# TAStm32_v4.net
KiCad netlist of a schematic drawn in EAGLE
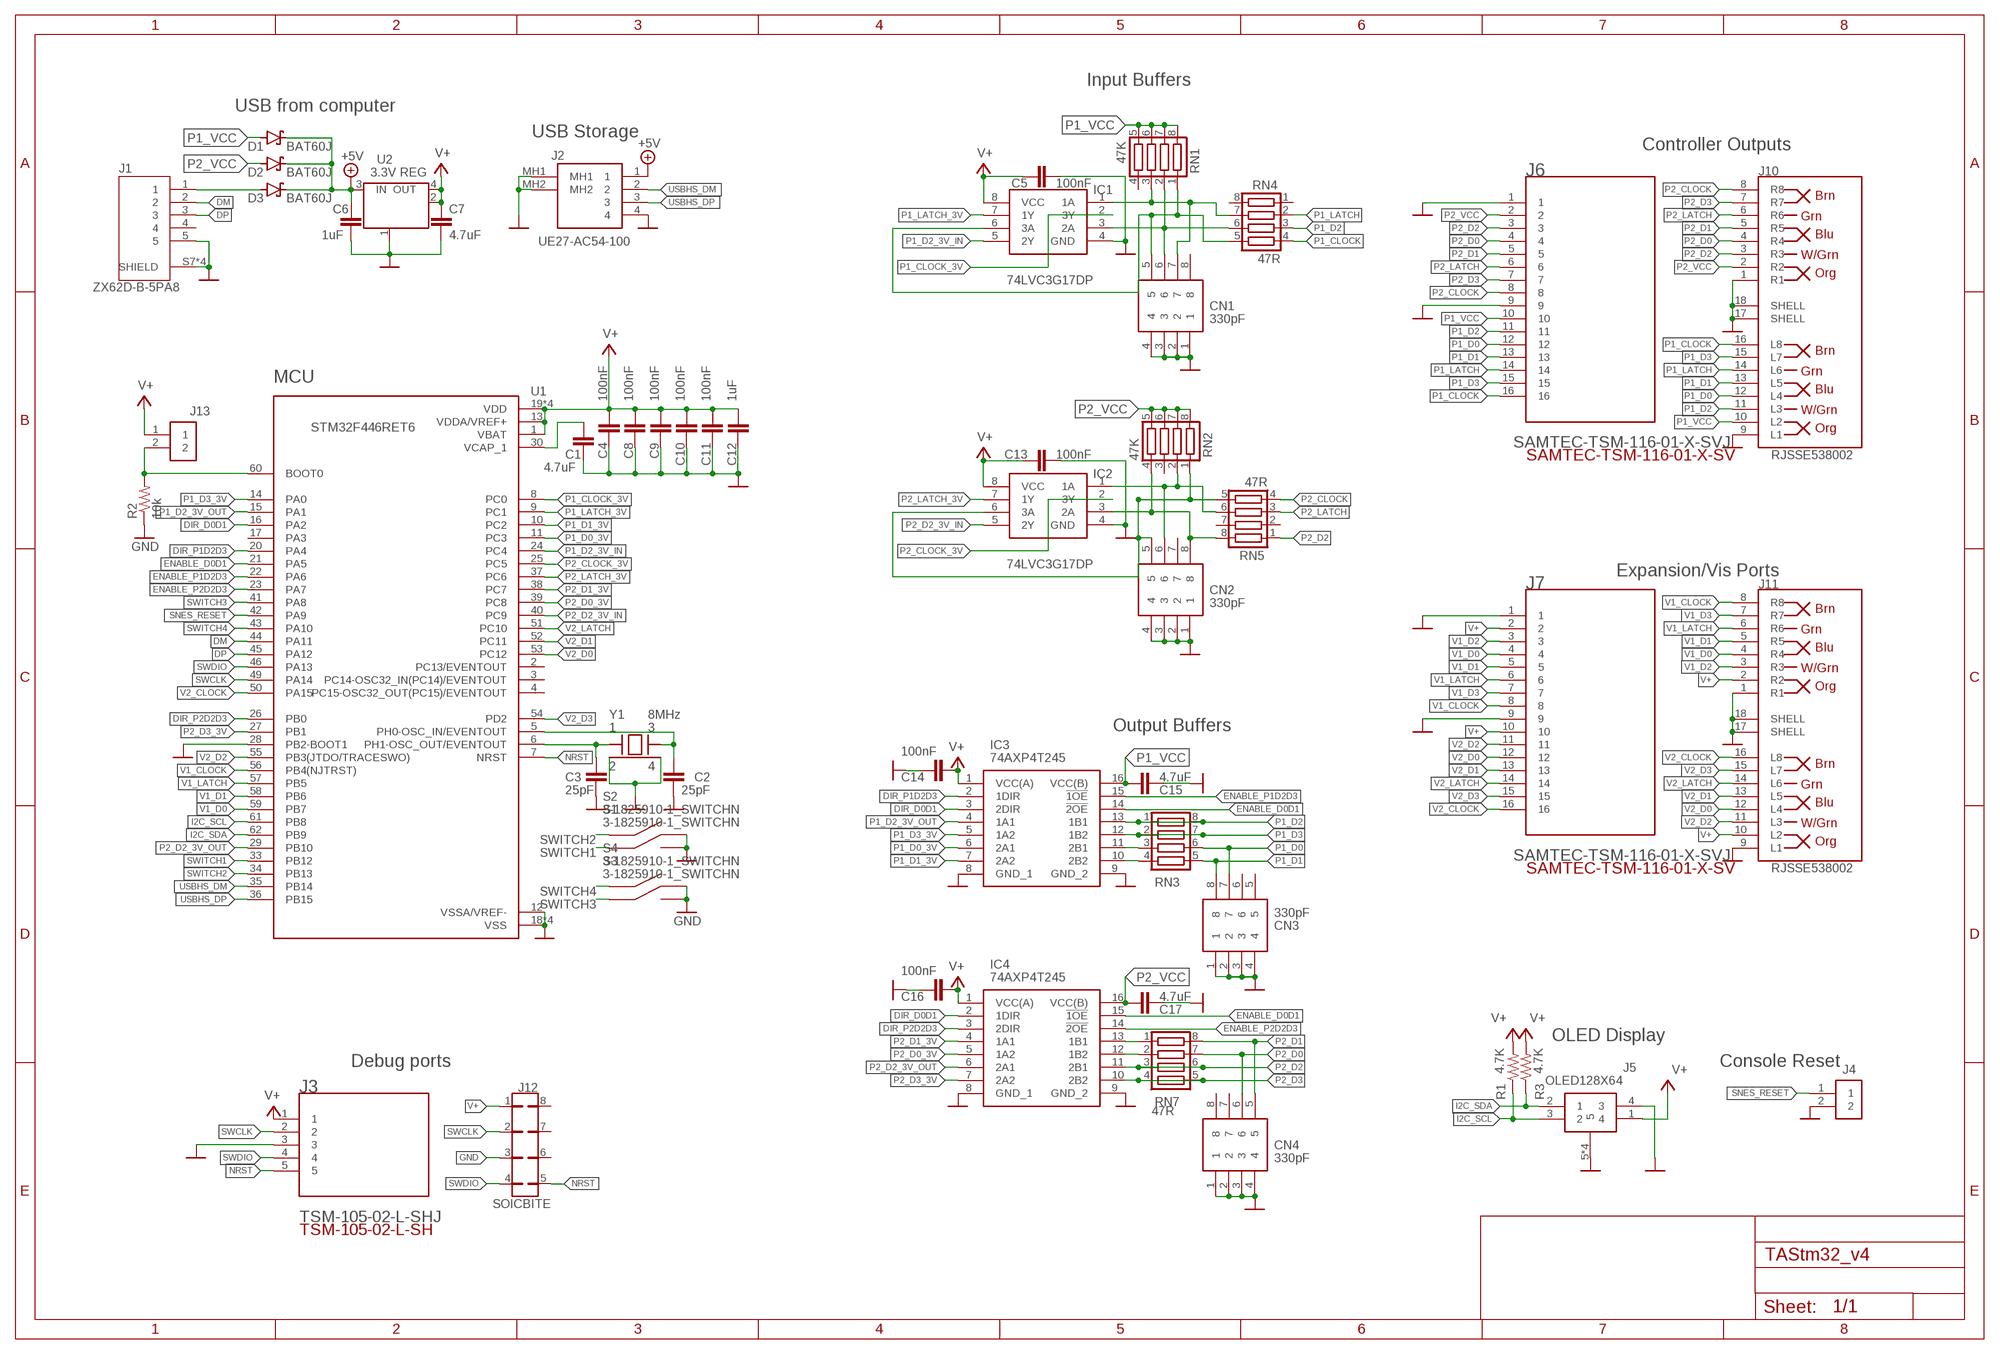
[diagram p0: schematic, sheet 1]

(export (version "E")
  (design (tool "Eeschema 10.0.6"))
  (components
    (comp (ref "C1")
      (value "4.7uF")
      (footprint "eagle-import:C0603K")
      (libsource (lib "eagle-import") (part "C-EUC0603K"))
    )
    (comp (ref "C2")
      (value "25pF")
      (footprint "eagle-import:C0603K")
      (libsource (lib "eagle-import") (part "C-EUC0603K"))
    )
    (comp (ref "C3")
      (value "25pF")
      (footprint "eagle-import:C0603K")
      (libsource (lib "eagle-import") (part "C-EUC0603K"))
    )
    (comp (ref "C4")
      (value "100nF")
      (footprint "eagle-import:C0603K")
      (libsource (lib "eagle-import") (part "C-EUC0603K"))
    )
    (comp (ref "C5")
      (value "100nF")
      (footprint "eagle-import:C0603K")
      (libsource (lib "eagle-import") (part "C-EUC0603K"))
    )
    (comp (ref "C6")
      (value "1uF")
      (footprint "eagle-import:C0603K")
      (libsource (lib "eagle-import") (part "C-EUC0603K"))
    )
    (comp (ref "C7")
      (value "4.7uF")
      (footprint "eagle-import:C0603K")
      (libsource (lib "eagle-import") (part "C-EUC0603K"))
    )
    (comp (ref "C8")
      (value "100nF")
      (footprint "eagle-import:C0603K")
      (libsource (lib "eagle-import") (part "C-EUC0603K"))
    )
    (comp (ref "C9")
      (value "100nF")
      (footprint "eagle-import:C0603K")
      (libsource (lib "eagle-import") (part "C-EUC0603K"))
    )
    (comp (ref "C10")
      (value "100nF")
      (footprint "eagle-import:C0603K")
      (libsource (lib "eagle-import") (part "C-EUC0603K"))
    )
    (comp (ref "C11")
      (value "100nF")
      (footprint "eagle-import:C0603K")
      (libsource (lib "eagle-import") (part "C-EUC0603K"))
    )
    (comp (ref "C12")
      (value "1uF")
      (footprint "eagle-import:C0603K")
      (libsource (lib "eagle-import") (part "C-EUC0603K"))
    )
    (comp (ref "C13")
      (value "100nF")
      (footprint "eagle-import:C0603K")
      (libsource (lib "eagle-import") (part "C-EUC0603K"))
    )
    (comp (ref "C14")
      (value "100nF")
      (footprint "eagle-import:C0603K")
      (libsource (lib "eagle-import") (part "C-EUC0603K"))
    )
    (comp (ref "C15")
      (value "4.7uF")
      (footprint "eagle-import:C0603K")
      (libsource (lib "eagle-import") (part "C-EUC0603K"))
    )
    (comp (ref "C16")
      (value "100nF")
      (footprint "eagle-import:C0603K")
      (libsource (lib "eagle-import") (part "C-EUC0603K"))
    )
    (comp (ref "C17")
      (value "4.7uF")
      (footprint "eagle-import:C0603K")
      (libsource (lib "eagle-import") (part "C-EUC0603K"))
    )
    (comp (ref "CN1")
      (value "330pF")
      (footprint "eagle-import:CA0612KRX7R7BB104")
      (fields
        (field (name "MANUFACTURER_PART_NUMBER") "CA0612KRX7R7BB104")
        (field (name "MOUSER_PART_NUMBER") "603-CA612KRX7R7BB104")
      )
      (libsource (lib "eagle-import") (part "CA0612KRX7R7BB104"))
    )
    (comp (ref "CN2")
      (value "330pF")
      (footprint "eagle-import:CA0612KRX7R7BB104")
      (fields
        (field (name "MANUFACTURER_PART_NUMBER") "CA0612KRX7R7BB104")
        (field (name "MOUSER_PART_NUMBER") "603-CA612KRX7R7BB104")
      )
      (libsource (lib "eagle-import") (part "CA0612KRX7R7BB104"))
    )
    (comp (ref "CN3")
      (value "330pF")
      (footprint "eagle-import:CA0612KRX7R7BB104")
      (fields
        (field (name "MANUFACTURER_PART_NUMBER") "CA0612KRX7R7BB104")
        (field (name "MOUSER_PART_NUMBER") "603-CA612KRX7R7BB104")
      )
      (libsource (lib "eagle-import") (part "CA0612KRX7R7BB104"))
    )
    (comp (ref "CN4")
      (value "330pF")
      (footprint "eagle-import:CA0612KRX7R7BB104")
      (fields
        (field (name "MANUFACTURER_PART_NUMBER") "CA0612KRX7R7BB104")
        (field (name "MOUSER_PART_NUMBER") "603-CA612KRX7R7BB104")
      )
      (libsource (lib "eagle-import") (part "CA0612KRX7R7BB104"))
    )
    (comp (ref "D1")
      (value "BAT60J")
      (footprint "eagle-import:DIODE_SOD323_ST")
      (libsource (lib "eagle-import") (part "DIODE_BAT60J"))
    )
    (comp (ref "D2")
      (value "BAT60J")
      (footprint "eagle-import:DIODE_SOD323_ST")
      (libsource (lib "eagle-import") (part "DIODE_BAT60J"))
    )
    (comp (ref "D3")
      (value "BAT60J")
      (footprint "eagle-import:DIODE_SOD323_ST")
      (libsource (lib "eagle-import") (part "DIODE_BAT60J"))
    )
    (comp (ref "IC1")
      (value "74LVC3G17DP")
      (footprint "eagle-import:SOP65P400X110-8N")
      (fields
        (field (name "MANUFACTURER_PART_NUMBER") "74HCT3G07DP-Q100H")
        (field (name "RS_PART_NUMBER") "1532947P")
      )
      (libsource (lib "eagle-import") (part "74HCT3G07DP-Q100H"))
    )
    (comp (ref "IC2")
      (value "74LVC3G17DP")
      (footprint "eagle-import:SOP65P400X110-8N")
      (fields
        (field (name "MANUFACTURER_PART_NUMBER") "74HCT3G07DP-Q100H")
        (field (name "RS_PART_NUMBER") "1532947P")
      )
      (libsource (lib "eagle-import") (part "74HCT3G07DP-Q100H"))
    )
    (comp (ref "IC3")
      (value "74AXP4T245")
      (footprint "eagle-import:SOP65P640X110-16N")
      (fields
        (field (name "MANUFACTURER_PART_NUMBER") "74AVCH4T245PW,118")
        (field (name "MOUSER_PART_NUMBER") "771-74AVCH4T245PW118")
      )
      (libsource (lib "eagle-import") (part "74AVCH4T245PW,118"))
    )
    (comp (ref "IC4")
      (value "74AXP4T245")
      (footprint "eagle-import:SOP65P640X110-16N")
      (fields
        (field (name "MANUFACTURER_PART_NUMBER") "74AVCH4T245PW,118")
        (field (name "MOUSER_PART_NUMBER") "771-74AVCH4T245PW118")
      )
      (libsource (lib "eagle-import") (part "74AVCH4T245PW,118"))
    )
    (comp (ref "J1")
      (value "ZX62D-B-5PA8")
      (footprint "eagle-import:HIROSE_ZX62D-B-5PA8")
      (fields (field (name "MF") "Hirose"))
      (libsource (lib "eagle-import") (part "ZX62D-B-5PA8"))
    )
    (comp (ref "J2")
      (value "UE27-AC54-100")
      (footprint "eagle-import:UE27AC54100")
      (fields (field (name "MOUSER_PART_NUMBER") "523-UE27-AC54-100"))
      (libsource (lib "eagle-import") (part "UE27-AC54-100"))
    )
    (comp (ref "J3")
      (value "TSM-105-02-L-SHJ")
      (footprint "eagle-import:TSM-105-02-L-SH")
      (fields (field (name "MF") "Samtec") (field (name "MP") "TSM-105-02-L-SH"))
      (libsource (lib "eagle-import") (part "TSM-105-02-L-SHJ"))
    )
    (comp (ref "J4")
      (value "CONSOLE_RESET")
      (footprint "eagle-import:SAMTEC-TSM-102-01-X-SH")
      (libsource (lib "eagle-import") (part "SAMTEC-TSM-102-01-X-SH_SAMTEC-TSM-102-01-X-SH"))
    )
    (comp (ref "J5")
      (value "OLED128X64")
      (footprint "eagle-import:OLED")
      (libsource (lib "eagle-import") (part "OLED128X64"))
    )
    (comp (ref "J6")
      (value "SAMTEC-TSM-116-01-X-SVJ")
      (footprint "eagle-import:SAMTEC-TSM-116-01-X-SV")
      (libsource (lib "eagle-import") (part "SAMTEC-TSM-116-01-X-SVJ"))
    )
    (comp (ref "J7")
      (value "SAMTEC-TSM-116-01-X-SVJ")
      (footprint "eagle-import:SAMTEC-TSM-116-01-X-SV")
      (libsource (lib "eagle-import") (part "SAMTEC-TSM-116-01-X-SVJ"))
    )
    (comp (ref "J10")
      (value "RJSSE538002")
      (footprint "eagle-import:AMPHENOL_RJSSE538002")
      (libsource (lib "eagle-import") (part "RJSSE538002_RJSSE538002"))
    )
    (comp (ref "J11")
      (value "RJSSE538002")
      (footprint "eagle-import:AMPHENOL_RJSSE538002")
      (libsource (lib "eagle-import") (part "RJSSE538002_RJSSE538002"))
    )
    (comp (ref "J12")
      (value "SOICBITE")
      (footprint "eagle-import:SOICBITE")
      (libsource (lib "eagle-import") (part "SOICBITE"))
    )
    (comp (ref "J13")
      (value "CONSOLE_RESET")
      (footprint "eagle-import:SAMTEC-TSM-102-01-X-SH")
      (libsource (lib "eagle-import") (part "SAMTEC-TSM-102-01-X-SH_SAMTEC-TSM-102-01-X-SH"))
    )
    (comp (ref "R1")
      (value "4.7K")
      (footprint "eagle-import:R0805")
      (libsource (lib "eagle-import") (part "R-US_R0805"))
    )
    (comp (ref "R2")
      (value "10k")
      (footprint "eagle-import:R0805")
      (libsource (lib "eagle-import") (part "R-US_R0805"))
    )
    (comp (ref "R3")
      (value "4.7K")
      (footprint "eagle-import:R0805")
      (libsource (lib "eagle-import") (part "R-US_R0805"))
    )
    (comp (ref "RN1")
      (value "47K")
      (footprint "eagle-import:CTS742C083")
      (libsource (lib "eagle-import") (part "CTS742C083"))
    )
    (comp (ref "RN2")
      (value "47K")
      (footprint "eagle-import:CTS742C083")
      (libsource (lib "eagle-import") (part "CTS742C083"))
    )
    (comp (ref "RN3")
      (value "CTS742C083")
      (footprint "eagle-import:CTS742C083")
      (libsource (lib "eagle-import") (part "CTS742C083"))
    )
    (comp (ref "RN4")
      (value "47R")
      (footprint "eagle-import:CTS742C083")
      (libsource (lib "eagle-import") (part "CTS742C083"))
    )
    (comp (ref "RN5")
      (value "47R")
      (footprint "eagle-import:CTS742C083")
      (libsource (lib "eagle-import") (part "CTS742C083"))
    )
    (comp (ref "RN7")
      (value "47R")
      (footprint "eagle-import:CTS742C083")
      (libsource (lib "eagle-import") (part "CTS742C083"))
    )
    (comp (ref "S1")
      (value "3-1825910-1_SWITCHN")
      (footprint "eagle-import:3-1825910-1_318259101")
      (libsource (lib "eagle-import") (part "3-1825910-1_SWITCHN"))
    )
    (comp (ref "S2")
      (value "3-1825910-1_SWITCHN")
      (footprint "eagle-import:3-1825910-1_318259101")
      (libsource (lib "eagle-import") (part "3-1825910-1_SWITCHN"))
    )
    (comp (ref "S3")
      (value "3-1825910-1_SWITCHN")
      (footprint "eagle-import:3-1825910-1_318259101")
      (libsource (lib "eagle-import") (part "3-1825910-1_SWITCHN"))
    )
    (comp (ref "S4")
      (value "3-1825910-1_SWITCHN")
      (footprint "eagle-import:3-1825910-1_318259101")
      (libsource (lib "eagle-import") (part "3-1825910-1_SWITCHN"))
    )
    (comp (ref "U1")
      (value "STM32F446RET6")
      (footprint "eagle-import:QFP50P1200X1200X160-64N")
      (libsource (lib "eagle-import") (part "STM32F446RET7"))
    )
    (comp (ref "U2")
      (value "3.3V REG")
      (footprint "eagle-import:SOT223")
      (libsource (lib "eagle-import") (part "MC33269ST-3.3T3"))
    )
    (comp (ref "Y1")
      (value "8MHz")
      (footprint "eagle-import:DFN-4")
      (libsource (lib "eagle-import") (part "ABMM-8.000MHZ-B2-T_ABMM-8.000MHZ-B2-T"))
    )
  )
  (nets
    (net (code "1") (name "+5V") (class "Default")
      (node (ref "C6") (pin "2") (pinfunction "2_2") (pintype "passive"))
      (node (ref "D1") (pin "C") (pinfunction "C_C") (pintype "passive"))
      (node (ref "D2") (pin "C") (pinfunction "C_C") (pintype "passive"))
      (node (ref "D3") (pin "C") (pinfunction "C_C") (pintype "passive"))
      (node (ref "J2") (pin "1") (pinfunction "1_1") (pintype "bidirectional"))
      (node (ref "U2") (pin "3") (pinfunction "IN_3") (pintype "input"))
    )
    (net (code "2") (name "DIR_D0D1") (class "Default")
      (node (ref "IC3") (pin "3") (pinfunction "2DIR_3") (pintype "bidirectional"))
      (node (ref "IC4") (pin "2") (pinfunction "1DIR_2") (pintype "bidirectional"))
      (node (ref "U1") (pin "16") (pinfunction "PA2_16") (pintype "bidirectional"))
    )
    (net (code "3") (name "DIR_P1D2D3") (class "Default")
      (node (ref "IC3") (pin "2") (pinfunction "1DIR_2") (pintype "bidirectional"))
      (node (ref "U1") (pin "20") (pinfunction "PA4_20") (pintype "bidirectional"))
    )
    (net (code "4") (name "DIR_P2D2D3") (class "Default")
      (node (ref "IC4") (pin "3") (pinfunction "2DIR_3") (pintype "bidirectional"))
      (node (ref "U1") (pin "26") (pinfunction "PB0_26") (pintype "bidirectional"))
    )
    (net (code "5") (name "DM") (class "Default")
      (node (ref "J1") (pin "2") (pinfunction "2_2") (pintype "passive"))
      (node (ref "U1") (pin "44") (pinfunction "PA11_44") (pintype "bidirectional"))
    )
    (net (code "6") (name "DP") (class "Default")
      (node (ref "J1") (pin "3") (pinfunction "3_3") (pintype "passive"))
      (node (ref "U1") (pin "45") (pinfunction "PA12_45") (pintype "bidirectional"))
    )
    (net (code "7") (name "ENABLE_D0D1") (class "Default")
      (node (ref "IC3") (pin "14") (pinfunction "~{2OE}_14") (pintype "bidirectional"))
      (node (ref "IC4") (pin "15") (pinfunction "~{1OE}_15") (pintype "bidirectional"))
      (node (ref "U1") (pin "21") (pinfunction "PA5_21") (pintype "bidirectional"))
    )
    (net (code "8") (name "ENABLE_P1D2D3") (class "Default")
      (node (ref "IC3") (pin "15") (pinfunction "~{1OE}_15") (pintype "bidirectional"))
      (node (ref "U1") (pin "22") (pinfunction "PA6_22") (pintype "bidirectional"))
    )
    (net (code "9") (name "ENABLE_P2D2D3") (class "Default")
      (node (ref "IC4") (pin "14") (pinfunction "~{2OE}_14") (pintype "bidirectional"))
      (node (ref "U1") (pin "23") (pinfunction "PA7_23") (pintype "bidirectional"))
    )
    (net (code "10") (name "GND") (class "Default")
      (node (ref "C1") (pin "2") (pinfunction "2_2") (pintype "passive"))
      (node (ref "C10") (pin "1") (pinfunction "1_1") (pintype "passive"))
      (node (ref "C11") (pin "1") (pinfunction "1_1") (pintype "passive"))
      (node (ref "C12") (pin "1") (pinfunction "1_1") (pintype "passive"))
      (node (ref "C13") (pin "2") (pinfunction "2_2") (pintype "passive"))
      (node (ref "C14") (pin "1") (pinfunction "1_1") (pintype "passive"))
      (node (ref "C15") (pin "2") (pinfunction "2_2") (pintype "passive"))
      (node (ref "C16") (pin "1") (pinfunction "1_1") (pintype "passive"))
      (node (ref "C17") (pin "2") (pinfunction "2_2") (pintype "passive"))
      (node (ref "C2") (pin "1") (pinfunction "1_1") (pintype "passive"))
      (node (ref "C3") (pin "1") (pinfunction "1_1") (pintype "passive"))
      (node (ref "C4") (pin "1") (pinfunction "1_1") (pintype "passive"))
      (node (ref "C5") (pin "2") (pinfunction "2_2") (pintype "passive"))
      (node (ref "C6") (pin "1") (pinfunction "1_1") (pintype "passive"))
      (node (ref "C7") (pin "1") (pinfunction "1_1") (pintype "passive"))
      (node (ref "C8") (pin "1") (pinfunction "1_1") (pintype "passive"))
      (node (ref "C9") (pin "1") (pinfunction "1_1") (pintype "passive"))
      (node (ref "CN1") (pin "1") (pinfunction "1_1") (pintype "bidirectional"))
      (node (ref "CN1") (pin "2") (pinfunction "2_2") (pintype "bidirectional"))
      (node (ref "CN1") (pin "3") (pinfunction "3_3") (pintype "bidirectional"))
      (node (ref "CN1") (pin "4") (pinfunction "4_4") (pintype "bidirectional"))
      (node (ref "CN2") (pin "1") (pinfunction "1_1") (pintype "bidirectional"))
      (node (ref "CN2") (pin "2") (pinfunction "2_2") (pintype "bidirectional"))
      (node (ref "CN2") (pin "3") (pinfunction "3_3") (pintype "bidirectional"))
      (node (ref "CN2") (pin "4") (pinfunction "4_4") (pintype "bidirectional"))
      (node (ref "CN3") (pin "1") (pinfunction "1_1") (pintype "bidirectional"))
      (node (ref "CN3") (pin "2") (pinfunction "2_2") (pintype "bidirectional"))
      (node (ref "CN3") (pin "3") (pinfunction "3_3") (pintype "bidirectional"))
      (node (ref "CN3") (pin "4") (pinfunction "4_4") (pintype "bidirectional"))
      (node (ref "CN4") (pin "1") (pinfunction "1_1") (pintype "bidirectional"))
      (node (ref "CN4") (pin "2") (pinfunction "2_2") (pintype "bidirectional"))
      (node (ref "CN4") (pin "3") (pinfunction "3_3") (pintype "bidirectional"))
      (node (ref "CN4") (pin "4") (pinfunction "4_4") (pintype "bidirectional"))
      (node (ref "IC1") (pin "4") (pinfunction "GND_4") (pintype "bidirectional"))
      (node (ref "IC2") (pin "4") (pinfunction "GND_4") (pintype "bidirectional"))
      (node (ref "IC3") (pin "8") (pinfunction "GND_1_8") (pintype "bidirectional"))
      (node (ref "IC3") (pin "9") (pinfunction "GND_2_9") (pintype "bidirectional"))
      (node (ref "IC4") (pin "8") (pinfunction "GND_1_8") (pintype "bidirectional"))
      (node (ref "IC4") (pin "9") (pinfunction "GND_2_9") (pintype "bidirectional"))
      (node (ref "J1") (pin "5") (pinfunction "5_5") (pintype "passive"))
      (node (ref "J1") (pin "S10") (pinfunction "SHIELD_S10") (pintype "power_in"))
      (node (ref "J1") (pin "S7") (pinfunction "SHIELD_S7") (pintype "power_in"))
      (node (ref "J1") (pin "S8") (pinfunction "SHIELD_S8") (pintype "power_in"))
      (node (ref "J1") (pin "S9") (pinfunction "SHIELD_S9") (pintype "power_in"))
      (node (ref "J10") (pin "1") (pinfunction "R1_1") (pintype "bidirectional"))
      (node (ref "J10") (pin "17") (pinfunction "SHELL_17") (pintype "passive"))
      (node (ref "J10") (pin "18") (pinfunction "SHELL_18") (pintype "passive"))
      (node (ref "J10") (pin "9") (pinfunction "L1_9") (pintype "bidirectional"))
      (node (ref "J11") (pin "1") (pinfunction "R1_1") (pintype "bidirectional"))
      (node (ref "J11") (pin "17") (pinfunction "SHELL_17") (pintype "passive"))
      (node (ref "J11") (pin "18") (pinfunction "SHELL_18") (pintype "passive"))
      (node (ref "J11") (pin "9") (pinfunction "L1_9") (pintype "bidirectional"))
      (node (ref "J12") (pin "3") (pinfunction "P$3_3") (pintype "passive"))
      (node (ref "J2") (pin "4") (pinfunction "4_4") (pintype "bidirectional"))
      (node (ref "J2") (pin "MH1") (pinfunction "MH1_MH1") (pintype "bidirectional"))
      (node (ref "J2") (pin "MH2") (pinfunction "MH2_MH2") (pintype "bidirectional"))
      (node (ref "J3") (pin "3") (pinfunction "3_3") (pintype "bidirectional"))
      (node (ref "J4") (pin "2") (pinfunction "2_2") (pintype "bidirectional"))
      (node (ref "J5") (pin "4") (pinfunction "3_4") (pintype "bidirectional"))
      (node (ref "J5") (pin "5") (pinfunction "5_5") (pintype "bidirectional"))
      (node (ref "J5") (pin "6") (pinfunction "5_6") (pintype "bidirectional"))
      (node (ref "J5") (pin "7") (pinfunction "5_7") (pintype "bidirectional"))
      (node (ref "J5") (pin "8") (pinfunction "5_8") (pintype "bidirectional"))
      (node (ref "J6") (pin "1") (pinfunction "1_1") (pintype "bidirectional"))
      (node (ref "J6") (pin "9") (pinfunction "9_9") (pintype "bidirectional"))
      (node (ref "J7") (pin "1") (pinfunction "1_1") (pintype "bidirectional"))
      (node (ref "J7") (pin "9") (pinfunction "9_9") (pintype "bidirectional"))
      (node (ref "R2") (pin "1") (pinfunction "1_1") (pintype "passive"))
      (node (ref "S1") (pin "3") (pinfunction "P$2_3") (pintype "bidirectional"))
      (node (ref "S1") (pin "4") (pinfunction "P$2_4") (pintype "bidirectional"))
      (node (ref "S2") (pin "3") (pinfunction "P$2_3") (pintype "bidirectional"))
      (node (ref "S2") (pin "4") (pinfunction "P$2_4") (pintype "bidirectional"))
      (node (ref "S3") (pin "3") (pinfunction "P$2_3") (pintype "bidirectional"))
      (node (ref "S3") (pin "4") (pinfunction "P$2_4") (pintype "bidirectional"))
      (node (ref "S4") (pin "3") (pinfunction "P$2_3") (pintype "bidirectional"))
      (node (ref "S4") (pin "4") (pinfunction "P$2_4") (pintype "bidirectional"))
      (node (ref "U1") (pin "12") (pinfunction "VSSA/VREF-_12") (pintype "power_in"))
      (node (ref "U1") (pin "18") (pinfunction "VSS_18") (pintype "power_in"))
      (node (ref "U1") (pin "28") (pinfunction "PB2-BOOT1_28") (pintype "bidirectional"))
      (node (ref "U1") (pin "31") (pinfunction "VSS_31") (pintype "power_in"))
      (node (ref "U1") (pin "47") (pinfunction "VSS_47") (pintype "power_in"))
      (node (ref "U1") (pin "63") (pinfunction "VSS_63") (pintype "power_in"))
      (node (ref "U2") (pin "1") (pinfunction "GND/ADJ_1") (pintype "input"))
      (node (ref "Y1") (pin "2") (pinfunction "2_2") (pintype "bidirectional"))
      (node (ref "Y1") (pin "4") (pinfunction "4_4") (pintype "bidirectional"))
    )
    (net (code "11") (name "I2C_SCL") (class "Default")
      (node (ref "J5") (pin "3") (pinfunction "2_3") (pintype "bidirectional"))
      (node (ref "R1") (pin "1") (pinfunction "1_1") (pintype "passive"))
      (node (ref "U1") (pin "61") (pinfunction "PB8_61") (pintype "bidirectional"))
    )
    (net (code "12") (name "I2C_SDA") (class "Default")
      (node (ref "J5") (pin "2") (pinfunction "1_2") (pintype "bidirectional"))
      (node (ref "R3") (pin "1") (pinfunction "1_1") (pintype "passive"))
      (node (ref "U1") (pin "62") (pinfunction "PB9_62") (pintype "bidirectional"))
    )
    (net (code "13") (name "NRST") (class "Default")
      (node (ref "J12") (pin "5") (pinfunction "P$5_5") (pintype "passive"))
      (node (ref "J3") (pin "5") (pinfunction "5_5") (pintype "bidirectional"))
      (node (ref "U1") (pin "7") (pinfunction "NRST_7") (pintype "bidirectional"))
    )
    (net (code "14") (name "Net-(D3-PadA)") (class "Default")
      (node (ref "D3") (pin "A") (pinfunction "A_A") (pintype "passive"))
      (node (ref "J1") (pin "1") (pinfunction "1_1") (pintype "passive"))
    )
    (net (code "15") (name "Net-(IC1-1A)") (class "Default")
      (node (ref "CN1") (pin "7") (pinfunction "7_7") (pintype "bidirectional"))
      (node (ref "IC1") (pin "1") (pinfunction "1A_1") (pintype "bidirectional"))
      (node (ref "RN1") (pin "3") (pinfunction "3_3") (pintype "passive"))
      (node (ref "RN4") (pin "7") (pinfunction "7_7") (pintype "passive"))
    )
    (net (code "16") (name "Net-(IC1-2A)") (class "Default")
      (node (ref "CN1") (pin "6") (pinfunction "6_6") (pintype "bidirectional"))
      (node (ref "IC1") (pin "3") (pinfunction "2A_3") (pintype "bidirectional"))
      (node (ref "RN1") (pin "2") (pinfunction "2_2") (pintype "passive"))
      (node (ref "RN4") (pin "6") (pinfunction "6_6") (pintype "passive"))
    )
    (net (code "17") (name "Net-(IC1-3A)") (class "Default")
      (node (ref "CN1") (pin "5") (pinfunction "5_5") (pintype "bidirectional"))
      (node (ref "IC1") (pin "6") (pinfunction "3A_6") (pintype "bidirectional"))
      (node (ref "RN1") (pin "1") (pinfunction "1_1") (pintype "passive"))
      (node (ref "RN4") (pin "5") (pinfunction "5_5") (pintype "passive"))
    )
    (net (code "18") (name "Net-(IC2-1A)") (class "Default")
      (node (ref "CN2") (pin "6") (pinfunction "6_6") (pintype "bidirectional"))
      (node (ref "IC2") (pin "1") (pinfunction "1A_1") (pintype "bidirectional"))
      (node (ref "RN2") (pin "2") (pinfunction "2_2") (pintype "passive"))
      (node (ref "RN5") (pin "6") (pinfunction "6_6") (pintype "passive"))
    )
    (net (code "19") (name "Net-(IC2-2A)") (class "Default")
      (node (ref "CN2") (pin "8") (pinfunction "8_8") (pintype "bidirectional"))
      (node (ref "IC2") (pin "3") (pinfunction "2A_3") (pintype "bidirectional"))
      (node (ref "RN2") (pin "4") (pinfunction "4_4") (pintype "passive"))
      (node (ref "RN5") (pin "8") (pinfunction "8_8") (pintype "passive"))
    )
    (net (code "20") (name "Net-(IC2-3A)") (class "Default")
      (node (ref "CN2") (pin "5") (pinfunction "5_5") (pintype "bidirectional"))
      (node (ref "IC2") (pin "6") (pinfunction "3A_6") (pintype "bidirectional"))
      (node (ref "RN2") (pin "1") (pinfunction "1_1") (pintype "passive"))
      (node (ref "RN5") (pin "5") (pinfunction "5_5") (pintype "passive"))
    )
    (net (code "21") (name "Net-(IC3-2B1)") (class "Default")
      (node (ref "IC3") (pin "11") (pinfunction "2B1_11") (pintype "bidirectional"))
      (node (ref "RN3") (pin "3") (pinfunction "3_3") (pintype "passive"))
    )
    (net (code "22") (name "Net-(IC3-2B2)") (class "Default")
      (node (ref "IC3") (pin "10") (pinfunction "2B2_10") (pintype "bidirectional"))
      (node (ref "RN3") (pin "4") (pinfunction "4_4") (pintype "passive"))
    )
    (net (code "23") (name "Net-(IC4-1B1)") (class "Default")
      (node (ref "IC4") (pin "13") (pinfunction "1B1_13") (pintype "bidirectional"))
      (node (ref "RN7") (pin "1") (pinfunction "1_1") (pintype "passive"))
    )
    (net (code "24") (name "Net-(IC4-1B2)") (class "Default")
      (node (ref "IC4") (pin "12") (pinfunction "1B2_12") (pintype "bidirectional"))
      (node (ref "RN7") (pin "2") (pinfunction "2_2") (pintype "passive"))
    )
    (net (code "25") (name "Net-(U1-BOOT0)") (class "Default")
      (node (ref "J13") (pin "2") (pinfunction "2_2") (pintype "bidirectional"))
      (node (ref "R2") (pin "2") (pinfunction "2_2") (pintype "passive"))
      (node (ref "U1") (pin "60") (pinfunction "BOOT0_60") (pintype "input"))
    )
    (net (code "26") (name "Net-(U1-PH0-OSC_IN{slash}EVENTOUT)") (class "Default")
      (node (ref "C2") (pin "2") (pinfunction "2_2") (pintype "passive"))
      (node (ref "U1") (pin "5") (pinfunction "PH0-OSC_IN/EVENTOUT_5") (pintype "bidirectional"))
      (node (ref "Y1") (pin "3") (pinfunction "3_3") (pintype "bidirectional"))
    )
    (net (code "27") (name "Net-(U1-PH1-OSC_OUT{slash}EVENTOUT)") (class "Default")
      (node (ref "C3") (pin "2") (pinfunction "2_2") (pintype "passive"))
      (node (ref "U1") (pin "6") (pinfunction "PH1-OSC_OUT/EVENTOUT_6") (pintype "bidirectional"))
      (node (ref "Y1") (pin "1") (pinfunction "1_1") (pintype "bidirectional"))
    )
    (net (code "28") (name "Net-(U1-VCAP_1)") (class "Default")
      (node (ref "C1") (pin "1") (pinfunction "1_1") (pintype "passive"))
      (node (ref "U1") (pin "30") (pinfunction "VCAP_1_30") (pintype "power_in"))
    )
    (net (code "29") (name "P1_CLOCK") (class "Default")
      (node (ref "J10") (pin "16") (pinfunction "L8_16") (pintype "bidirectional"))
      (node (ref "J6") (pin "16") (pinfunction "16_16") (pintype "bidirectional"))
      (node (ref "RN4") (pin "4") (pinfunction "4_4") (pintype "passive"))
    )
    (net (code "30") (name "P1_CLOCK_3V") (class "Default")
      (node (ref "IC1") (pin "2") (pinfunction "3Y_2") (pintype "bidirectional"))
      (node (ref "U1") (pin "8") (pinfunction "PC0_8") (pintype "bidirectional"))
    )
    (net (code "31") (name "P1_D0") (class "Default")
      (node (ref "CN3") (pin "7") (pinfunction "7_7") (pintype "bidirectional"))
      (node (ref "J10") (pin "12") (pinfunction "L4_12") (pintype "bidirectional"))
      (node (ref "J6") (pin "12") (pinfunction "12_12") (pintype "bidirectional"))
      (node (ref "RN3") (pin "6") (pinfunction "6_6") (pintype "passive"))
    )
    (net (code "32") (name "P1_D0_3V") (class "Default")
      (node (ref "IC3") (pin "6") (pinfunction "2A1_6") (pintype "bidirectional"))
      (node (ref "U1") (pin "11") (pinfunction "PC3_11") (pintype "bidirectional"))
    )
    (net (code "33") (name "P1_D1") (class "Default")
      (node (ref "CN3") (pin "8") (pinfunction "8_8") (pintype "bidirectional"))
      (node (ref "J10") (pin "13") (pinfunction "L5_13") (pintype "bidirectional"))
      (node (ref "J6") (pin "13") (pinfunction "13_13") (pintype "bidirectional"))
      (node (ref "RN3") (pin "5") (pinfunction "5_5") (pintype "passive"))
    )
    (net (code "34") (name "P1_D1_3V") (class "Default")
      (node (ref "IC3") (pin "7") (pinfunction "2A2_7") (pintype "bidirectional"))
      (node (ref "U1") (pin "10") (pinfunction "PC2_10") (pintype "bidirectional"))
    )
    (net (code "35") (name "P1_D2") (class "Default")
      (node (ref "IC3") (pin "13") (pinfunction "1B1_13") (pintype "bidirectional"))
      (node (ref "J10") (pin "11") (pinfunction "L3_11") (pintype "bidirectional"))
      (node (ref "J6") (pin "11") (pinfunction "11_11") (pintype "bidirectional"))
      (node (ref "RN3") (pin "1") (pinfunction "1_1") (pintype "passive"))
      (node (ref "RN3") (pin "8") (pinfunction "8_8") (pintype "passive"))
      (node (ref "RN4") (pin "3") (pinfunction "3_3") (pintype "passive"))
    )
    (net (code "36") (name "P1_D2_3V_IN") (class "Default")
      (node (ref "IC1") (pin "5") (pinfunction "2Y_5") (pintype "bidirectional"))
      (node (ref "U1") (pin "24") (pinfunction "PC4_24") (pintype "bidirectional"))
    )
    (net (code "37") (name "P1_D2_3V_OUT") (class "Default")
      (node (ref "IC3") (pin "4") (pinfunction "1A1_4") (pintype "bidirectional"))
      (node (ref "U1") (pin "15") (pinfunction "PA1_15") (pintype "bidirectional"))
    )
    (net (code "38") (name "P1_D3") (class "Default")
      (node (ref "IC3") (pin "12") (pinfunction "1B2_12") (pintype "bidirectional"))
      (node (ref "J10") (pin "15") (pinfunction "L7_15") (pintype "bidirectional"))
      (node (ref "J6") (pin "15") (pinfunction "15_15") (pintype "bidirectional"))
      (node (ref "RN3") (pin "2") (pinfunction "2_2") (pintype "passive"))
      (node (ref "RN3") (pin "7") (pinfunction "7_7") (pintype "passive"))
    )
    (net (code "39") (name "P1_D3_3V") (class "Default")
      (node (ref "IC3") (pin "5") (pinfunction "1A2_5") (pintype "bidirectional"))
      (node (ref "U1") (pin "14") (pinfunction "PA0_14") (pintype "bidirectional"))
    )
    (net (code "40") (name "P1_LATCH") (class "Default")
      (node (ref "J10") (pin "14") (pinfunction "L6_14") (pintype "bidirectional"))
      (node (ref "J6") (pin "14") (pinfunction "14_14") (pintype "bidirectional"))
      (node (ref "RN4") (pin "2") (pinfunction "2_2") (pintype "passive"))
    )
    (net (code "41") (name "P1_LATCH_3V") (class "Default")
      (node (ref "IC1") (pin "7") (pinfunction "1Y_7") (pintype "bidirectional"))
      (node (ref "U1") (pin "9") (pinfunction "PC1_9") (pintype "bidirectional"))
    )
    (net (code "42") (name "P1_VCC") (class "Default")
      (node (ref "C15") (pin "1") (pinfunction "1_1") (pintype "passive"))
      (node (ref "D1") (pin "A") (pinfunction "A_A") (pintype "passive"))
      (node (ref "IC3") (pin "16") (pinfunction "VCC(B)_16") (pintype "bidirectional"))
      (node (ref "J10") (pin "10") (pinfunction "L2_10") (pintype "bidirectional"))
      (node (ref "J6") (pin "10") (pinfunction "10_10") (pintype "bidirectional"))
      (node (ref "RN1") (pin "5") (pinfunction "5_5") (pintype "passive"))
      (node (ref "RN1") (pin "6") (pinfunction "6_6") (pintype "passive"))
      (node (ref "RN1") (pin "7") (pinfunction "7_7") (pintype "passive"))
      (node (ref "RN1") (pin "8") (pinfunction "8_8") (pintype "passive"))
    )
    (net (code "43") (name "P2_CLOCK") (class "Default")
      (node (ref "J10") (pin "8") (pinfunction "R8_8") (pintype "bidirectional"))
      (node (ref "J6") (pin "8") (pinfunction "8_8") (pintype "bidirectional"))
      (node (ref "RN5") (pin "4") (pinfunction "4_4") (pintype "passive"))
    )
    (net (code "44") (name "P2_CLOCK_3V") (class "Default")
      (node (ref "IC2") (pin "2") (pinfunction "3Y_2") (pintype "bidirectional"))
      (node (ref "U1") (pin "25") (pinfunction "PC5_25") (pintype "bidirectional"))
    )
    (net (code "45") (name "P2_D0") (class "Default")
      (node (ref "CN4") (pin "6") (pinfunction "6_6") (pintype "bidirectional"))
      (node (ref "J10") (pin "4") (pinfunction "R4_4") (pintype "bidirectional"))
      (node (ref "J6") (pin "4") (pinfunction "4_4") (pintype "bidirectional"))
      (node (ref "RN7") (pin "7") (pinfunction "7_7") (pintype "passive"))
    )
    (net (code "46") (name "P2_D0_3V") (class "Default")
      (node (ref "IC4") (pin "5") (pinfunction "1A2_5") (pintype "bidirectional"))
      (node (ref "U1") (pin "39") (pinfunction "PC8_39") (pintype "bidirectional"))
    )
    (net (code "47") (name "P2_D1") (class "Default")
      (node (ref "CN4") (pin "5") (pinfunction "5_5") (pintype "bidirectional"))
      (node (ref "J10") (pin "5") (pinfunction "R5_5") (pintype "bidirectional"))
      (node (ref "J6") (pin "5") (pinfunction "5_5") (pintype "bidirectional"))
      (node (ref "RN7") (pin "8") (pinfunction "8_8") (pintype "passive"))
    )
    (net (code "48") (name "P2_D1_3V") (class "Default")
      (node (ref "IC4") (pin "4") (pinfunction "1A1_4") (pintype "bidirectional"))
      (node (ref "U1") (pin "38") (pinfunction "PC7_38") (pintype "bidirectional"))
    )
    (net (code "49") (name "P2_D2") (class "Default")
      (node (ref "IC4") (pin "11") (pinfunction "2B1_11") (pintype "bidirectional"))
      (node (ref "J10") (pin "3") (pinfunction "R3_3") (pintype "bidirectional"))
      (node (ref "J6") (pin "3") (pinfunction "3_3") (pintype "bidirectional"))
      (node (ref "RN5") (pin "1") (pinfunction "1_1") (pintype "passive"))
      (node (ref "RN7") (pin "3") (pinfunction "3_3") (pintype "passive"))
      (node (ref "RN7") (pin "6") (pinfunction "6_6") (pintype "passive"))
    )
    (net (code "50") (name "P2_D2_3V_IN") (class "Default")
      (node (ref "IC2") (pin "5") (pinfunction "2Y_5") (pintype "bidirectional"))
      (node (ref "U1") (pin "40") (pinfunction "PC9_40") (pintype "bidirectional"))
    )
    (net (code "51") (name "P2_D2_3V_OUT") (class "Default")
      (node (ref "IC4") (pin "6") (pinfunction "2A1_6") (pintype "bidirectional"))
      (node (ref "U1") (pin "29") (pinfunction "PB10_29") (pintype "bidirectional"))
    )
    (net (code "52") (name "P2_D3") (class "Default")
      (node (ref "IC4") (pin "10") (pinfunction "2B2_10") (pintype "bidirectional"))
      (node (ref "J10") (pin "7") (pinfunction "R7_7") (pintype "bidirectional"))
      (node (ref "J6") (pin "7") (pinfunction "7_7") (pintype "bidirectional"))
      (node (ref "RN7") (pin "4") (pinfunction "4_4") (pintype "passive"))
      (node (ref "RN7") (pin "5") (pinfunction "5_5") (pintype "passive"))
    )
    (net (code "53") (name "P2_D3_3V") (class "Default")
      (node (ref "IC4") (pin "7") (pinfunction "2A2_7") (pintype "bidirectional"))
      (node (ref "U1") (pin "27") (pinfunction "PB1_27") (pintype "bidirectional"))
    )
    (net (code "54") (name "P2_LATCH") (class "Default")
      (node (ref "J10") (pin "6") (pinfunction "R6_6") (pintype "bidirectional"))
      (node (ref "J6") (pin "6") (pinfunction "6_6") (pintype "bidirectional"))
      (node (ref "RN5") (pin "3") (pinfunction "3_3") (pintype "passive"))
    )
    (net (code "55") (name "P2_LATCH_3V") (class "Default")
      (node (ref "IC2") (pin "7") (pinfunction "1Y_7") (pintype "bidirectional"))
      (node (ref "U1") (pin "37") (pinfunction "PC6_37") (pintype "bidirectional"))
    )
    (net (code "56") (name "P2_VCC") (class "Default")
      (node (ref "C17") (pin "1") (pinfunction "1_1") (pintype "passive"))
      (node (ref "D2") (pin "A") (pinfunction "A_A") (pintype "passive"))
      (node (ref "IC4") (pin "16") (pinfunction "VCC(B)_16") (pintype "bidirectional"))
      (node (ref "J10") (pin "2") (pinfunction "R2_2") (pintype "bidirectional"))
      (node (ref "J6") (pin "2") (pinfunction "2_2") (pintype "bidirectional"))
      (node (ref "RN2") (pin "5") (pinfunction "5_5") (pintype "passive"))
      (node (ref "RN2") (pin "6") (pinfunction "6_6") (pintype "passive"))
      (node (ref "RN2") (pin "7") (pinfunction "7_7") (pintype "passive"))
      (node (ref "RN2") (pin "8") (pinfunction "8_8") (pintype "passive"))
    )
    (net (code "57") (name "SNES_RESET") (class "Default")
      (node (ref "J4") (pin "1") (pinfunction "1_1") (pintype "bidirectional"))
      (node (ref "U1") (pin "42") (pinfunction "PA9_42") (pintype "bidirectional"))
    )
    (net (code "58") (name "SWCLK") (class "Default")
      (node (ref "J12") (pin "2") (pinfunction "P$2_2") (pintype "passive"))
      (node (ref "J3") (pin "2") (pinfunction "2_2") (pintype "bidirectional"))
      (node (ref "U1") (pin "49") (pinfunction "PA14_49") (pintype "bidirectional"))
    )
    (net (code "59") (name "SWDIO") (class "Default")
      (node (ref "J12") (pin "4") (pinfunction "P$4_4") (pintype "passive"))
      (node (ref "J3") (pin "4") (pinfunction "4_4") (pintype "bidirectional"))
      (node (ref "U1") (pin "46") (pinfunction "PA13_46") (pintype "bidirectional"))
    )
    (net (code "60") (name "SWITCH1") (class "Default")
      (node (ref "S1") (pin "1") (pinfunction "P$1_1") (pintype "bidirectional"))
      (node (ref "S1") (pin "2") (pinfunction "P$1_2") (pintype "bidirectional"))
      (node (ref "U1") (pin "33") (pinfunction "PB12_33") (pintype "bidirectional"))
    )
    (net (code "61") (name "SWITCH2") (class "Default")
      (node (ref "S2") (pin "1") (pinfunction "P$1_1") (pintype "bidirectional"))
      (node (ref "S2") (pin "2") (pinfunction "P$1_2") (pintype "bidirectional"))
      (node (ref "U1") (pin "34") (pinfunction "PB13_34") (pintype "bidirectional"))
    )
    (net (code "62") (name "SWITCH3") (class "Default")
      (node (ref "S3") (pin "1") (pinfunction "P$1_1") (pintype "bidirectional"))
      (node (ref "S3") (pin "2") (pinfunction "P$1_2") (pintype "bidirectional"))
      (node (ref "U1") (pin "41") (pinfunction "PA8_41") (pintype "bidirectional"))
    )
    (net (code "63") (name "SWITCH4") (class "Default")
      (node (ref "S4") (pin "1") (pinfunction "P$1_1") (pintype "bidirectional"))
      (node (ref "S4") (pin "2") (pinfunction "P$1_2") (pintype "bidirectional"))
      (node (ref "U1") (pin "43") (pinfunction "PA10_43") (pintype "bidirectional"))
    )
    (net (code "64") (name "USBHS_DM") (class "Default")
      (node (ref "J2") (pin "2") (pinfunction "2_2") (pintype "bidirectional"))
      (node (ref "U1") (pin "35") (pinfunction "PB14_35") (pintype "bidirectional"))
    )
    (net (code "65") (name "USBHS_DP") (class "Default")
      (node (ref "J2") (pin "3") (pinfunction "3_3") (pintype "bidirectional"))
      (node (ref "U1") (pin "36") (pinfunction "PB15_36") (pintype "bidirectional"))
    )
    (net (code "66") (name "V+") (class "Default")
      (node (ref "C10") (pin "2") (pinfunction "2_2") (pintype "passive"))
      (node (ref "C11") (pin "2") (pinfunction "2_2") (pintype "passive"))
      (node (ref "C12") (pin "2") (pinfunction "2_2") (pintype "passive"))
      (node (ref "C13") (pin "1") (pinfunction "1_1") (pintype "passive"))
      (node (ref "C14") (pin "2") (pinfunction "2_2") (pintype "passive"))
      (node (ref "C16") (pin "2") (pinfunction "2_2") (pintype "passive"))
      (node (ref "C4") (pin "2") (pinfunction "2_2") (pintype "passive"))
      (node (ref "C5") (pin "1") (pinfunction "1_1") (pintype "passive"))
      (node (ref "C7") (pin "2") (pinfunction "2_2") (pintype "passive"))
      (node (ref "C8") (pin "2") (pinfunction "2_2") (pintype "passive"))
      (node (ref "C9") (pin "2") (pinfunction "2_2") (pintype "passive"))
      (node (ref "IC1") (pin "8") (pinfunction "VCC_8") (pintype "bidirectional"))
      (node (ref "IC2") (pin "8") (pinfunction "VCC_8") (pintype "bidirectional"))
      (node (ref "IC3") (pin "1") (pinfunction "VCC(A)_1") (pintype "bidirectional"))
      (node (ref "IC4") (pin "1") (pinfunction "VCC(A)_1") (pintype "bidirectional"))
      (node (ref "J11") (pin "10") (pinfunction "L2_10") (pintype "bidirectional"))
      (node (ref "J11") (pin "2") (pinfunction "R2_2") (pintype "bidirectional"))
      (node (ref "J12") (pin "1") (pinfunction "P$1_1") (pintype "passive"))
      (node (ref "J13") (pin "1") (pinfunction "1_1") (pintype "bidirectional"))
      (node (ref "J3") (pin "1") (pinfunction "1_1") (pintype "bidirectional"))
      (node (ref "J5") (pin "1") (pinfunction "4_1") (pintype "bidirectional"))
      (node (ref "J7") (pin "10") (pinfunction "10_10") (pintype "bidirectional"))
      (node (ref "J7") (pin "2") (pinfunction "2_2") (pintype "bidirectional"))
      (node (ref "R1") (pin "2") (pinfunction "2_2") (pintype "passive"))
      (node (ref "R3") (pin "2") (pinfunction "2_2") (pintype "passive"))
      (node (ref "U1") (pin "1") (pinfunction "VBAT_1") (pintype "power_in"))
      (node (ref "U1") (pin "13") (pinfunction "VDDA/VREF+_13") (pintype "power_in"))
      (node (ref "U1") (pin "19") (pinfunction "VDD_19") (pintype "power_in"))
      (node (ref "U1") (pin "32") (pinfunction "VDD_32") (pintype "power_in"))
      (node (ref "U1") (pin "48") (pinfunction "VDD_48") (pintype "power_in"))
      (node (ref "U1") (pin "64") (pinfunction "VDD_64") (pintype "power_in"))
      (node (ref "U2") (pin "2") (pinfunction "OUT_2") (pintype "passive"))
      (node (ref "U2") (pin "4") (pinfunction "OUT_4") (pintype "passive"))
    )
    (net (code "67") (name "V1_CLOCK") (class "Default")
      (node (ref "J11") (pin "8") (pinfunction "R8_8") (pintype "bidirectional"))
      (node (ref "J7") (pin "8") (pinfunction "8_8") (pintype "bidirectional"))
      (node (ref "U1") (pin "56") (pinfunction "PB4(NJTRST)_56") (pintype "bidirectional"))
    )
    (net (code "68") (name "V1_D0") (class "Default")
      (node (ref "J11") (pin "4") (pinfunction "R4_4") (pintype "bidirectional"))
      (node (ref "J7") (pin "4") (pinfunction "4_4") (pintype "bidirectional"))
      (node (ref "U1") (pin "59") (pinfunction "PB7_59") (pintype "bidirectional"))
    )
    (net (code "69") (name "V1_D1") (class "Default")
      (node (ref "J11") (pin "5") (pinfunction "R5_5") (pintype "bidirectional"))
      (node (ref "J7") (pin "5") (pinfunction "5_5") (pintype "bidirectional"))
      (node (ref "U1") (pin "58") (pinfunction "PB6_58") (pintype "bidirectional"))
    )
    (net (code "70") (name "V1_D2") (class "Default")
      (node (ref "J11") (pin "3") (pinfunction "R3_3") (pintype "bidirectional"))
      (node (ref "J7") (pin "3") (pinfunction "3_3") (pintype "bidirectional"))
    )
    (net (code "71") (name "V1_D3") (class "Default")
      (node (ref "J11") (pin "7") (pinfunction "R7_7") (pintype "bidirectional"))
      (node (ref "J7") (pin "7") (pinfunction "7_7") (pintype "bidirectional"))
    )
    (net (code "72") (name "V1_LATCH") (class "Default")
      (node (ref "J11") (pin "6") (pinfunction "R6_6") (pintype "bidirectional"))
      (node (ref "J7") (pin "6") (pinfunction "6_6") (pintype "bidirectional"))
      (node (ref "U1") (pin "57") (pinfunction "PB5_57") (pintype "bidirectional"))
    )
    (net (code "73") (name "V2_CLOCK") (class "Default")
      (node (ref "J11") (pin "16") (pinfunction "L8_16") (pintype "bidirectional"))
      (node (ref "J7") (pin "16") (pinfunction "16_16") (pintype "bidirectional"))
      (node (ref "U1") (pin "50") (pinfunction "PA15_50") (pintype "bidirectional"))
    )
    (net (code "74") (name "V2_D0") (class "Default")
      (node (ref "J11") (pin "12") (pinfunction "L4_12") (pintype "bidirectional"))
      (node (ref "J7") (pin "12") (pinfunction "12_12") (pintype "bidirectional"))
      (node (ref "U1") (pin "53") (pinfunction "PC12_53") (pintype "bidirectional"))
    )
    (net (code "75") (name "V2_D1") (class "Default")
      (node (ref "J11") (pin "13") (pinfunction "L5_13") (pintype "bidirectional"))
      (node (ref "J7") (pin "13") (pinfunction "13_13") (pintype "bidirectional"))
      (node (ref "U1") (pin "52") (pinfunction "PC11_52") (pintype "bidirectional"))
    )
    (net (code "76") (name "V2_D2") (class "Default")
      (node (ref "J11") (pin "11") (pinfunction "L3_11") (pintype "bidirectional"))
      (node (ref "J7") (pin "11") (pinfunction "11_11") (pintype "bidirectional"))
      (node (ref "U1") (pin "55") (pinfunction "PB3(JTDO/TRACESWO)_55") (pintype "bidirectional"))
    )
    (net (code "77") (name "V2_D3") (class "Default")
      (node (ref "J11") (pin "15") (pinfunction "L7_15") (pintype "bidirectional"))
      (node (ref "J7") (pin "15") (pinfunction "15_15") (pintype "bidirectional"))
      (node (ref "U1") (pin "54") (pinfunction "PD2_54") (pintype "bidirectional"))
    )
    (net (code "78") (name "V2_LATCH") (class "Default")
      (node (ref "J11") (pin "14") (pinfunction "L6_14") (pintype "bidirectional"))
      (node (ref "J7") (pin "14") (pinfunction "14_14") (pintype "bidirectional"))
      (node (ref "U1") (pin "51") (pinfunction "PC10_51") (pintype "bidirectional"))
    )
    (net (code "79") (name "unconnected-(CN1-Pad8)") (class "Default")
      (node (ref "CN1") (pin "8") (pinfunction "8_8") (pintype "bidirectional"))
    )
    (net (code "80") (name "unconnected-(CN2-Pad7)") (class "Default")
      (node (ref "CN2") (pin "7") (pinfunction "7_7") (pintype "bidirectional"))
    )
    (net (code "81") (name "unconnected-(CN3-Pad5)") (class "Default")
      (node (ref "CN3") (pin "5") (pinfunction "5_5") (pintype "bidirectional"))
    )
    (net (code "82") (name "unconnected-(CN3-Pad6)") (class "Default")
      (node (ref "CN3") (pin "6") (pinfunction "6_6") (pintype "bidirectional"))
    )
    (net (code "83") (name "unconnected-(CN4-Pad7)") (class "Default")
      (node (ref "CN4") (pin "7") (pinfunction "7_7") (pintype "bidirectional"))
    )
    (net (code "84") (name "unconnected-(CN4-Pad8)") (class "Default")
      (node (ref "CN4") (pin "8") (pinfunction "8_8") (pintype "bidirectional"))
    )
    (net (code "85") (name "unconnected-(J1-Pad4)") (class "Default")
      (node (ref "J1") (pin "4") (pinfunction "4_4") (pintype "passive"))
    )
    (net (code "86") (name "unconnected-(J12-P$6-Pad6)") (class "Default")
      (node (ref "J12") (pin "6") (pinfunction "P$6_6") (pintype "passive"))
    )
    (net (code "87") (name "unconnected-(J12-P$7-Pad7)") (class "Default")
      (node (ref "J12") (pin "7") (pinfunction "P$7_7") (pintype "passive"))
    )
    (net (code "88") (name "unconnected-(J12-P$8-Pad8)") (class "Default")
      (node (ref "J12") (pin "8") (pinfunction "P$8_8") (pintype "passive"))
    )
    (net (code "89") (name "unconnected-(RN1-Pad4)") (class "Default")
      (node (ref "RN1") (pin "4") (pinfunction "4_4") (pintype "passive"))
    )
    (net (code "90") (name "unconnected-(RN2-Pad3)") (class "Default")
      (node (ref "RN2") (pin "3") (pinfunction "3_3") (pintype "passive"))
    )
    (net (code "91") (name "unconnected-(RN4-Pad1)") (class "Default")
      (node (ref "RN4") (pin "1") (pinfunction "1_1") (pintype "passive"))
    )
    (net (code "92") (name "unconnected-(RN4-Pad8)") (class "Default")
      (node (ref "RN4") (pin "8") (pinfunction "8_8") (pintype "passive"))
    )
    (net (code "93") (name "unconnected-(RN5-Pad2)") (class "Default")
      (node (ref "RN5") (pin "2") (pinfunction "2_2") (pintype "passive"))
    )
    (net (code "94") (name "unconnected-(RN5-Pad7)") (class "Default")
      (node (ref "RN5") (pin "7") (pinfunction "7_7") (pintype "passive"))
    )
    (net (code "95") (name "unconnected-(U1-PA3-Pad17)") (class "Default")
      (node (ref "U1") (pin "17") (pinfunction "PA3_17") (pintype "bidirectional"))
    )
    (net (code "96") (name "unconnected-(U1-PC13{slash}EVENTOUT-Pad2)") (class "Default")
      (node (ref "U1") (pin "2") (pinfunction "PC13/EVENTOUT_2") (pintype "bidirectional"))
    )
    (net (code "97") (name "unconnected-(U1-PC14-OSC32_IN(PC14){slash}EVENTOUT-Pad3)") (class "Default")
      (node (ref "U1") (pin "3") (pinfunction "PC14-OSC32_IN(PC14)/EVENTOUT_3") (pintype "bidirectional"))
    )
    (net (code "98") (name "unconnected-(U1-PC15-OSC32_OUT(PC15){slash}EVENTOUT-Pad4)") (class "Default")
      (node (ref "U1") (pin "4") (pinfunction "PC15-OSC32_OUT(PC15)/EVENTOUT_4") (pintype "bidirectional"))
    )
  )
)
